# working.net
KiCad netlist of a schematic drawn in EAGLE
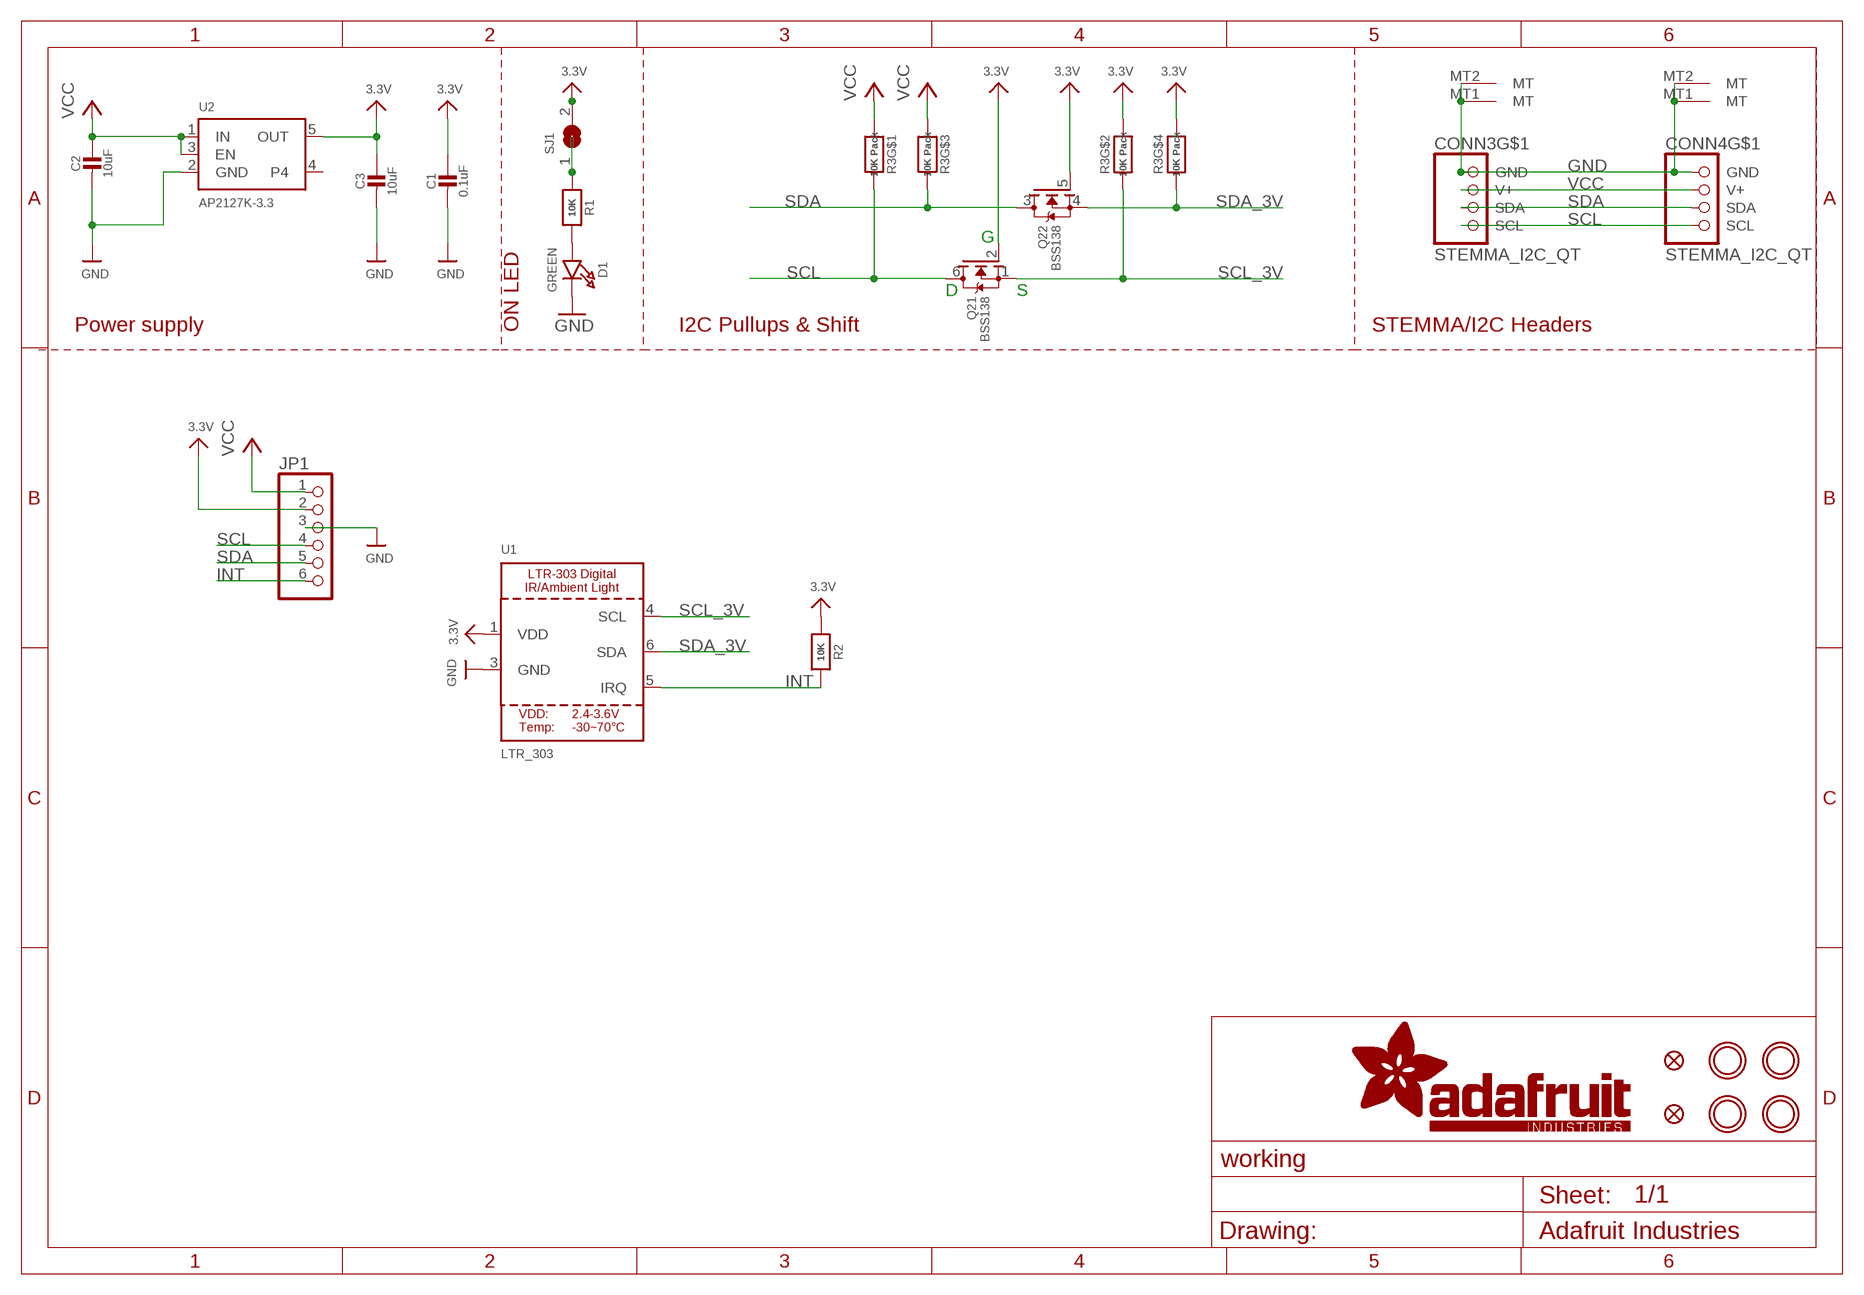
[diagram p0: schematic, sheet 1]

(export (version "E")
  (design (tool "Eeschema 10.0.6"))
  (components
    (comp (ref "C1")
      (value "0.1uF")
      (footprint "eagle-import:0603-NO")
      (libsource (lib "eagle-import") (part "CAP_CERAMIC0603_NO"))
    )
    (comp (ref "C2")
      (value "10uF")
      (footprint "eagle-import:0805-NO")
      (libsource (lib "eagle-import") (part "CAP_CERAMIC0805-NOOUTLINE"))
    )
    (comp (ref "C3")
      (value "10uF")
      (footprint "eagle-import:0805-NO")
      (libsource (lib "eagle-import") (part "CAP_CERAMIC0805-NOOUTLINE"))
    )
    (comp (ref "CONN3")
      (value "STEMMA_I2C_QT")
      (footprint "eagle-import:JST_SH4")
      (libsource (lib "eagle-import") (part "STEMMA_I2C_QT"))
    )
    (comp (ref "CONN4")
      (value "STEMMA_I2C_QT")
      (footprint "eagle-import:JST_SH4")
      (libsource (lib "eagle-import") (part "STEMMA_I2C_QT"))
    )
    (comp (ref "D1")
      (value "GREEN")
      (footprint "eagle-import:CHIPLED_0603_NOOUTLINE")
      (libsource (lib "eagle-import") (part "LED0603_NOOUTLINE"))
    )
    (comp (ref "FID3")
      (value "FIDUCIAL_1MM")
      (footprint "eagle-import:FIDUCIAL_1MM")
      (libsource (lib "eagle-import") (part "FIDUCIAL_1MM"))
    )
    (comp (ref "FID4")
      (value "FIDUCIAL_1MM")
      (footprint "eagle-import:FIDUCIAL_1MM")
      (libsource (lib "eagle-import") (part "FIDUCIAL_1MM"))
    )
    (comp (ref "JP1")
      (value "HEADER-1X670MIL")
      (footprint "eagle-import:1X06_ROUND_70")
      (libsource (lib "eagle-import") (part "HEADER-1X670MIL"))
    )
    (comp (ref "Q2")
      (value "BSS138")
      (footprint "eagle-import:SOT363")
      (libsource (lib "eagle-import") (part "MOSFET-N_DUAL"))
    )
    (comp (ref "R1")
      (value "10K")
      (footprint "eagle-import:0603-NO")
      (libsource (lib "eagle-import") (part "RESISTOR_0603_NOOUT"))
    )
    (comp (ref "R2")
      (value "10K")
      (footprint "eagle-import:0603-NO")
      (libsource (lib "eagle-import") (part "RESISTOR_0603_NOOUT"))
    )
    (comp (ref "R3")
      (value "10K Pack")
      (footprint "eagle-import:RESPACK_4X0603")
      (libsource (lib "eagle-import") (part "RESISTOR_4PACK"))
    )
    (comp (ref "SJ1")
      (value "SOLDERJUMPERCLOSED")
      (footprint "eagle-import:SOLDERJUMPER_CLOSEDWIRE")
      (libsource (lib "eagle-import") (part "SOLDERJUMPERCLOSED"))
    )
    (comp (ref "U$1")
      (value "MOUNTINGHOLE2.5")
      (footprint "eagle-import:MOUNTINGHOLE_2.5_PLATED")
      (libsource (lib "eagle-import") (part "MOUNTINGHOLE2.5"))
    )
    (comp (ref "U$17")
      (value "MOUNTINGHOLE2.5")
      (footprint "eagle-import:MOUNTINGHOLE_2.5_PLATED")
      (libsource (lib "eagle-import") (part "MOUNTINGHOLE2.5"))
    )
    (comp (ref "U$19")
      (value "MOUNTINGHOLE2.5")
      (footprint "eagle-import:MOUNTINGHOLE_2.5_PLATED")
      (libsource (lib "eagle-import") (part "MOUNTINGHOLE2.5"))
    )
    (comp (ref "U$21")
      (value "MOUNTINGHOLE2.5")
      (footprint "eagle-import:MOUNTINGHOLE_2.5_PLATED")
      (libsource (lib "eagle-import") (part "MOUNTINGHOLE2.5"))
    )
    (comp (ref "U1")
      (value "LTR_303")
      (footprint "eagle-import:LTR390")
      (libsource (lib "eagle-import") (part "LTR_303"))
    )
    (comp (ref "U2")
      (value "AP2127K-3.3")
      (footprint "eagle-import:SOT23-5")
      (libsource (lib "eagle-import") (part "VREG_SOT23-5"))
    )
  )
  (nets
    (net (code "1") (name "/INT") (class "Default")
      (node (ref "JP1") (pin "6") (pinfunction "6_6") (pintype "passive"))
      (node (ref "R2") (pin "2") (pinfunction "2_2") (pintype "passive"))
      (node (ref "U1") (pin "5") (pinfunction "IRQ_5") (pintype "output"))
    )
    (net (code "2") (name "/SCL") (class "Default")
      (node (ref "CONN3") (pin "4") (pinfunction "SCL_4") (pintype "passive"))
      (node (ref "CONN4") (pin "4") (pinfunction "SCL_4") (pintype "passive"))
      (node (ref "JP1") (pin "4") (pinfunction "4_4") (pintype "passive"))
      (node (ref "Q2") (pin "6") (pinfunction "D_6") (pintype "bidirectional"))
      (node (ref "R3") (pin "8") (pinfunction "2_8") (pintype "passive"))
    )
    (net (code "3") (name "/SCL_3V") (class "Default")
      (node (ref "Q2") (pin "1") (pinfunction "S_1") (pintype "bidirectional"))
      (node (ref "R3") (pin "7") (pinfunction "2_7") (pintype "passive"))
      (node (ref "U1") (pin "4") (pinfunction "SCL_4") (pintype "input"))
    )
    (net (code "4") (name "/SDA") (class "Default")
      (node (ref "CONN3") (pin "3") (pinfunction "SDA_3") (pintype "passive"))
      (node (ref "CONN4") (pin "3") (pinfunction "SDA_3") (pintype "passive"))
      (node (ref "JP1") (pin "5") (pinfunction "5_5") (pintype "passive"))
      (node (ref "Q2") (pin "3") (pinfunction "D_3") (pintype "bidirectional"))
      (node (ref "R3") (pin "6") (pinfunction "2_6") (pintype "passive"))
    )
    (net (code "5") (name "/SDA_3V") (class "Default")
      (node (ref "Q2") (pin "4") (pinfunction "S_4") (pintype "bidirectional"))
      (node (ref "R3") (pin "5") (pinfunction "2_5") (pintype "passive"))
      (node (ref "U1") (pin "6") (pinfunction "SDA_6") (pintype "bidirectional"))
    )
    (net (code "6") (name "3.3V") (class "Default")
      (node (ref "C1") (pin "1") (pinfunction "1_1") (pintype "passive"))
      (node (ref "C3") (pin "1") (pinfunction "1_1") (pintype "passive"))
      (node (ref "JP1") (pin "2") (pinfunction "2_2") (pintype "passive"))
      (node (ref "Q2") (pin "2") (pinfunction "G_2") (pintype "bidirectional"))
      (node (ref "Q2") (pin "5") (pinfunction "G_5") (pintype "bidirectional"))
      (node (ref "R2") (pin "1") (pinfunction "1_1") (pintype "passive"))
      (node (ref "R3") (pin "2") (pinfunction "1_2") (pintype "passive"))
      (node (ref "R3") (pin "4") (pinfunction "1_4") (pintype "passive"))
      (node (ref "SJ1") (pin "2") (pinfunction "2_2") (pintype "passive"))
      (node (ref "U1") (pin "1") (pinfunction "VDD_1") (pintype "power_in"))
      (node (ref "U2") (pin "5") (pinfunction "OUT_5") (pintype "power_in"))
    )
    (net (code "7") (name "GND") (class "Default")
      (node (ref "C1") (pin "2") (pinfunction "2_2") (pintype "passive"))
      (node (ref "C2") (pin "2") (pinfunction "2_2") (pintype "passive"))
      (node (ref "C3") (pin "2") (pinfunction "2_2") (pintype "passive"))
      (node (ref "CONN3") (pin "1") (pinfunction "GND_1") (pintype "passive"))
      (node (ref "CONN3") (pin "MT1") (pinfunction "MT_MT1") (pintype "bidirectional"))
      (node (ref "CONN3") (pin "MT2") (pinfunction "MT_MT2") (pintype "bidirectional"))
      (node (ref "CONN4") (pin "1") (pinfunction "GND_1") (pintype "passive"))
      (node (ref "CONN4") (pin "MT1") (pinfunction "MT_MT1") (pintype "bidirectional"))
      (node (ref "CONN4") (pin "MT2") (pinfunction "MT_MT2") (pintype "bidirectional"))
      (node (ref "D1") (pin "C") (pinfunction "C_C") (pintype "passive"))
      (node (ref "JP1") (pin "3") (pinfunction "3_3") (pintype "passive"))
      (node (ref "U1") (pin "3") (pinfunction "GND_3") (pintype "power_in"))
      (node (ref "U2") (pin "2") (pinfunction "GND_2") (pintype "power_in"))
    )
    (net (code "8") (name "Net-(D1-PadA)") (class "Default")
      (node (ref "D1") (pin "A") (pinfunction "A_A") (pintype "passive"))
      (node (ref "R1") (pin "2") (pinfunction "2_2") (pintype "passive"))
    )
    (net (code "9") (name "Net-(R1-Pad1)") (class "Default")
      (node (ref "R1") (pin "1") (pinfunction "1_1") (pintype "passive"))
      (node (ref "SJ1") (pin "1") (pinfunction "1_1") (pintype "passive"))
    )
    (net (code "10") (name "VCC") (class "Default")
      (node (ref "C2") (pin "1") (pinfunction "1_1") (pintype "passive"))
      (node (ref "CONN3") (pin "2") (pinfunction "V+_2") (pintype "passive"))
      (node (ref "CONN4") (pin "2") (pinfunction "V+_2") (pintype "passive"))
      (node (ref "JP1") (pin "1") (pinfunction "1_1") (pintype "passive"))
      (node (ref "R3") (pin "1") (pinfunction "1_1") (pintype "passive"))
      (node (ref "R3") (pin "3") (pinfunction "1_3") (pintype "passive"))
      (node (ref "U2") (pin "1") (pinfunction "IN_1") (pintype "power_in"))
      (node (ref "U2") (pin "3") (pinfunction "EN_3") (pintype "input"))
    )
    (net (code "11") (name "unconnected-(U2-P4-Pad4)") (class "Default")
      (node (ref "U2") (pin "4") (pinfunction "P4_4") (pintype "bidirectional"))
    )
  )
)
